# trigger.net
KiCad netlist of a schematic drawn in EAGLE
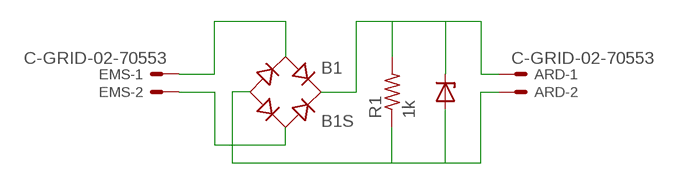
[diagram p0: schematic, sheet 1]

(export (version "E")
  (design (tool "Eeschema 10.0.6"))
  (components
    (comp (ref "ARD")
      (value "C-GRID-02-70553")
      (footprint "eagle-import:70553-02")
      (libsource (lib "eagle-import") (part "C-GRID-02-70553"))
    )
    (comp (ref "B1")
      (value "B1S")
      (footprint "eagle-import:MBS")
      (libsource (lib "eagle-import") (part "BS1"))
    )
    (comp (ref "EMS")
      (value "C-GRID-02-70553")
      (footprint "eagle-import:70553-02")
      (libsource (lib "eagle-import") (part "C-GRID-02-70553"))
    )
    (comp (ref "R1")
      (value "1k")
      (footprint "eagle-import:0207_12")
      (libsource (lib "eagle-import") (part "R-US_0207/12"))
    )
  )
  (nets
    (net (code "1") (name "Net-(ARDA-S)") (class "Default")
      (node (ref "ARD") (pin "1") (pinfunction "S_1") (pintype "passive"))
      (node (ref "B1") (pin "+") (pinfunction "+_+") (pintype "passive"))
      (node (ref "R1") (pin "2") (pinfunction "2_2") (pintype "passive"))
    )
    (net (code "2") (name "Net-(ARDB-S)") (class "Default")
      (node (ref "ARD") (pin "2") (pinfunction "S_2") (pintype "passive"))
      (node (ref "B1") (pin "-") (pinfunction "-_-") (pintype "passive"))
      (node (ref "R1") (pin "1") (pinfunction "1_1") (pintype "passive"))
    )
    (net (code "3") (name "Net-(EMSA-S)") (class "Default")
      (node (ref "B1") (pin "AC1") (pinfunction "AC1_AC1") (pintype "passive"))
      (node (ref "EMS") (pin "1") (pinfunction "S_1") (pintype "passive"))
    )
    (net (code "4") (name "Net-(EMSB-S)") (class "Default")
      (node (ref "B1") (pin "AC2") (pinfunction "AC2_AC2") (pintype "passive"))
      (node (ref "EMS") (pin "2") (pinfunction "S_2") (pintype "passive"))
    )
  )
)
